# 19V_Converter.net
KiCad netlist of a schematic drawn in Altium Designer
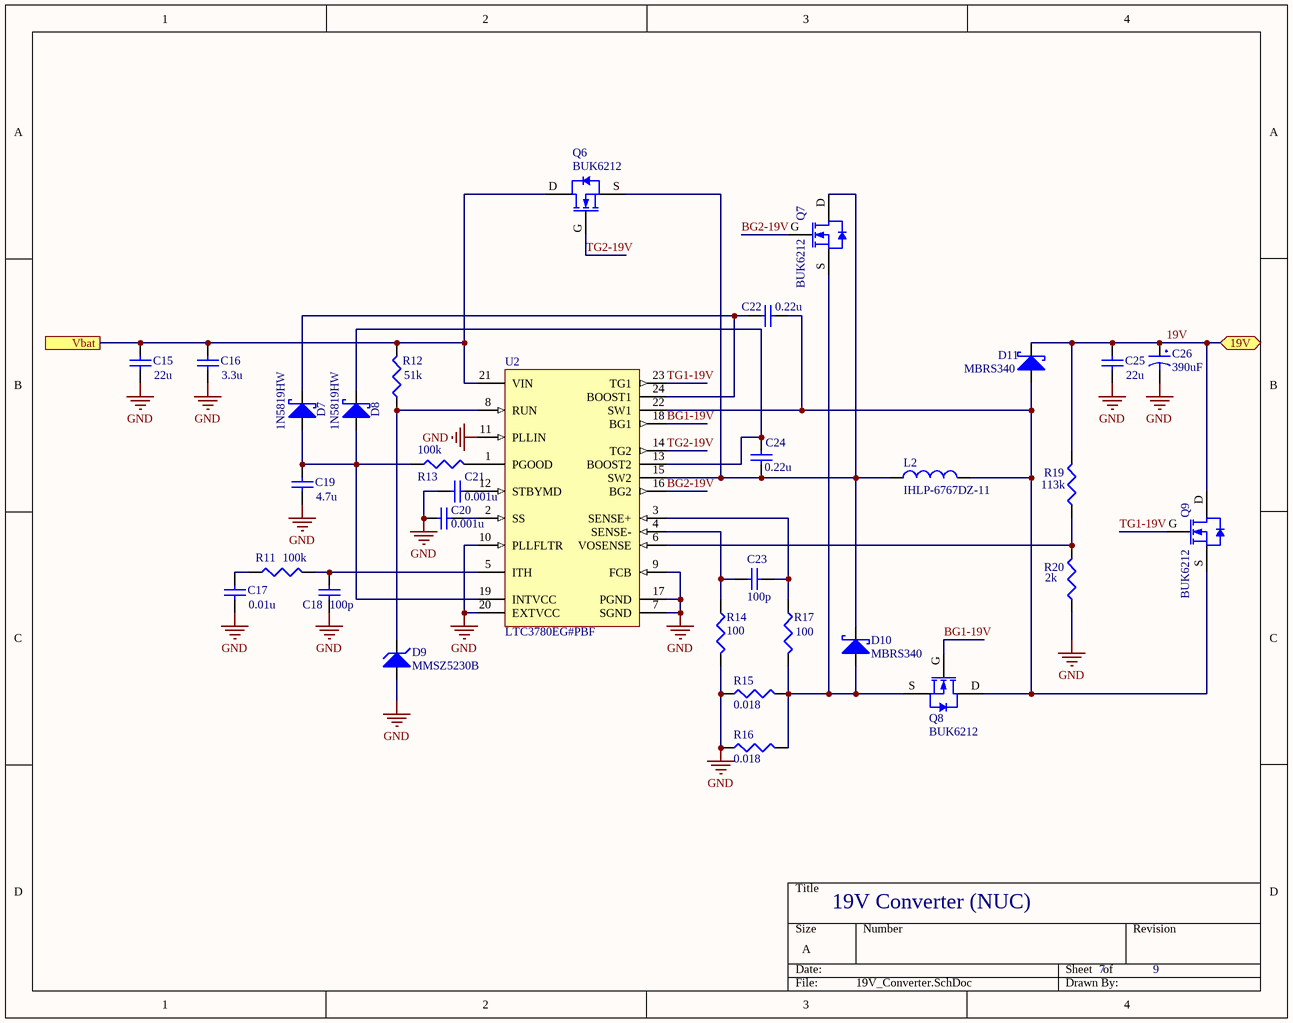
[diagram p0: 19V_Converter.SchDoc]

(export (version "E")
  (design (tool "Eeschema 10.0.6"))
  (components
    (comp (ref "C15")
      (value "22u")
      (footprint "C1206")
      (description "Capacitor (Semiconductor SIM Model)")
      (fields (field (name "Comment") "Cap Semi") (field (name "PUBLISHER") "Altium Limited"))
      (libsource (lib "Miscellaneous Devices") (part "Cap Semi"))
    )
    (comp (ref "C16")
      (value "3.3u")
      (footprint "C1206")
      (description "Capacitor (Semiconductor SIM Model)")
      (fields (field (name "Comment") "Cap Semi") (field (name "PUBLISHER") "Altium Limited"))
      (libsource (lib "Miscellaneous Devices") (part "Cap Semi"))
    )
    (comp (ref "C17")
      (value "0.01u")
      (footprint "C1206")
      (description "Capacitor (Semiconductor SIM Model)")
      (fields (field (name "Comment") "Cap Semi") (field (name "PUBLISHER") "Altium Limited"))
      (libsource (lib "Miscellaneous Devices") (part "Cap Semi"))
    )
    (comp (ref "C18")
      (value "100p")
      (footprint "C1206")
      (description "Capacitor (Semiconductor SIM Model)")
      (fields (field (name "Comment") "Cap Semi") (field (name "PUBLISHER") "Altium Limited"))
      (libsource (lib "Miscellaneous Devices") (part "Cap Semi"))
    )
    (comp (ref "C19")
      (value "4.7u")
      (footprint "C1206")
      (description "Capacitor (Semiconductor SIM Model)")
      (fields (field (name "Comment") "Cap Semi") (field (name "PUBLISHER") "Altium Limited"))
      (libsource (lib "Miscellaneous Devices") (part "Cap Semi"))
    )
    (comp (ref "C20")
      (value "0.001u")
      (footprint "C1206")
      (description "Capacitor (Semiconductor SIM Model)")
      (fields (field (name "Comment") "Cap Semi") (field (name "PUBLISHER") "Altium Limited"))
      (libsource (lib "Miscellaneous Devices") (part "Cap Semi"))
    )
    (comp (ref "C21")
      (value "0.001u")
      (footprint "C1206")
      (description "Capacitor (Semiconductor SIM Model)")
      (fields (field (name "Comment") "Cap Semi") (field (name "PUBLISHER") "Altium Limited"))
      (libsource (lib "Miscellaneous Devices") (part "Cap Semi"))
    )
    (comp (ref "C22")
      (value "0.22u")
      (footprint "C1206")
      (description "Capacitor (Semiconductor SIM Model)")
      (fields (field (name "Comment") "Cap Semi") (field (name "PUBLISHER") "Altium Limited"))
      (libsource (lib "Miscellaneous Devices") (part "Cap Semi"))
    )
    (comp (ref "C23")
      (value "100p")
      (footprint "C1206")
      (description "Capacitor (Semiconductor SIM Model)")
      (fields (field (name "Comment") "Cap Semi") (field (name "PUBLISHER") "Altium Limited"))
      (libsource (lib "Miscellaneous Devices") (part "Cap Semi"))
    )
    (comp (ref "C24")
      (value "0.22u")
      (footprint "C1206")
      (description "Capacitor (Semiconductor SIM Model)")
      (fields (field (name "Comment") "Cap Semi") (field (name "PUBLISHER") "Altium Limited"))
      (libsource (lib "Miscellaneous Devices") (part "Cap Semi"))
    )
    (comp (ref "C25")
      (value "22u")
      (footprint "C1206")
      (description "Capacitor (Semiconductor SIM Model)")
      (fields (field (name "Comment") "Cap Semi") (field (name "PUBLISHER") "Altium Limited"))
      (libsource (lib "Miscellaneous Devices") (part "Cap Semi"))
    )
    (comp (ref "C26")
      (value "390uF")
      (footprint "PCVxxxxxMCLxGS")
      (description "CAP ALUM POLY 390UF 20% 25V SMD")
      (libsource (lib "Power_Embedded_Board_Library") (part "PCV1E391MCL2GS"))
    )
    (comp (ref "D7")
      (value "1N5819HW")
      (footprint "1N58xx")
      (description "1A Schottky Barrier Rectifier Diode")
      (libsource (lib "Power_Embedded_Board_Library") (part "1N58xx"))
    )
    (comp (ref "D8")
      (value "1N5819HW")
      (footprint "1N58xx")
      (description "1A Schottky Barrier Rectifier Diode")
      (libsource (lib "Power_Embedded_Board_Library") (part "1N58xx"))
    )
    (comp (ref "D9")
      (value "MMSZ5230B")
      (footprint "ONSC-SOD-123-2-425-04_V")
      (description "Zener Voltage Regulator, 500 mW, 2-Pin SOD-123, Pb-Free, Tape and Reel")
      (fields (field (name "MANUFACTURER") "On Semiconductor") (field (name "PARTNUMBER") "MMSZ5230BT1G"))
      (libsource (lib "Power_Embedded_Board_Library") (part "MMSZ5230BT1G"))
    )
    (comp (ref "D10")
      (value "MBRS340")
      (footprint "MBRS340")
      (description "Schottky Rectifier")
      (libsource (lib "Power_Embedded_Board_Library") (part "MBRS340"))
    )
    (comp (ref "D11")
      (value "MBRS340")
      (footprint "MBRS340")
      (description "Schottky Rectifier")
      (libsource (lib "Power_Embedded_Board_Library") (part "MBRS340"))
    )
    (comp (ref "L2")
      (value "IHLP-6767DZ-11")
      (footprint "IHLP-6767DZ-11")
      (description "15µH Shielded Molded Inductor 14A 14.4 mOhm Max Nonstandard")
      (libsource (lib "Power_Embedded_Board_Library") (part "IHLP-6767DZ-11"))
    )
    (comp (ref "Q6")
      (value "BUK6212")
      (footprint "NXP-SOT428_M")
      (description "N-Channel TrenchMOS Intermediate Level FET, 40 V, 50 A, 3-Pin SOT428, Tape and Reel")
      (fields
        (field (name "MANUFACTURER") "NXP Semiconductors")
        (field (name "PARTNUMBER") "BUK6212-40C,118")
      )
      (libsource (lib "Power_Embedded_Board_Library") (part "BUK6212"))
    )
    (comp (ref "Q7")
      (value "BUK6212")
      (footprint "NXP-SOT428_M")
      (description "N-Channel TrenchMOS Intermediate Level FET, 40 V, 50 A, 3-Pin SOT428, Tape and Reel")
      (fields
        (field (name "MANUFACTURER") "NXP Semiconductors")
        (field (name "PARTNUMBER") "BUK6212-40C,118")
      )
      (libsource (lib "Power_Embedded_Board_Library") (part "BUK6212"))
    )
    (comp (ref "Q8")
      (value "BUK6212")
      (footprint "NXP-SOT428_M")
      (description "N-Channel TrenchMOS Intermediate Level FET, 40 V, 50 A, 3-Pin SOT428, Tape and Reel")
      (fields
        (field (name "MANUFACTURER") "NXP Semiconductors")
        (field (name "PARTNUMBER") "BUK6212-40C,118")
      )
      (libsource (lib "Power_Embedded_Board_Library") (part "BUK6212"))
    )
    (comp (ref "Q9")
      (value "BUK6212")
      (footprint "NXP-SOT428_M")
      (description "N-Channel TrenchMOS Intermediate Level FET, 40 V, 50 A, 3-Pin SOT428, Tape and Reel")
      (fields
        (field (name "MANUFACTURER") "NXP Semiconductors")
        (field (name "PARTNUMBER") "BUK6212-40C,118")
      )
      (libsource (lib "Power_Embedded_Board_Library") (part "BUK6212"))
    )
    (comp (ref "R11")
      (value "100k")
      (footprint "J1-0603")
      (description "Resistor")
      (fields (field (name "Comment") "Res3") (field (name "PUBLISHER") "Altium Limited"))
      (libsource (lib "Miscellaneous Devices") (part "Res3"))
    )
    (comp (ref "R12")
      (value "51k")
      (footprint "J1-0603")
      (description "Resistor")
      (fields (field (name "Comment") "Res3") (field (name "PUBLISHER") "Altium Limited"))
      (libsource (lib "Miscellaneous Devices") (part "Res3"))
    )
    (comp (ref "R13")
      (value "100k")
      (footprint "J1-0603")
      (description "Resistor")
      (fields (field (name "Comment") "Res3") (field (name "PUBLISHER") "Altium Limited"))
      (libsource (lib "Miscellaneous Devices") (part "Res3"))
    )
    (comp (ref "R14")
      (value "100")
      (footprint "J1-0603")
      (description "Resistor")
      (fields (field (name "Comment") "Res3") (field (name "PUBLISHER") "Altium Limited"))
      (libsource (lib "Miscellaneous Devices") (part "Res3"))
    )
    (comp (ref "R15")
      (value "0.018")
      (footprint "R1206")
      (description "Resistor")
      (fields (field (name "Comment") "Res3") (field (name "PUBLISHER") "Altium Limited"))
      (libsource (lib "Miscellaneous Devices") (part "Res3"))
    )
    (comp (ref "R16")
      (value "0.018")
      (footprint "R1206")
      (description "Resistor")
      (fields (field (name "Comment") "Res3") (field (name "PUBLISHER") "Altium Limited"))
      (libsource (lib "Miscellaneous Devices") (part "Res3"))
    )
    (comp (ref "R17")
      (value "100")
      (footprint "J1-0603")
      (description "Resistor")
      (fields (field (name "Comment") "Res3") (field (name "PUBLISHER") "Altium Limited"))
      (libsource (lib "Miscellaneous Devices") (part "Res3"))
    )
    (comp (ref "R19")
      (value "113k")
      (footprint "J1-0603")
      (description "Resistor")
      (fields (field (name "Comment") "Res3") (field (name "PUBLISHER") "Altium Limited"))
      (libsource (lib "Miscellaneous Devices") (part "Res3"))
    )
    (comp (ref "R20")
      (value "2k")
      (footprint "J1-0603")
      (description "Resistor")
      (fields (field (name "Comment") "Res3") (field (name "PUBLISHER") "Altium Limited"))
      (libsource (lib "Miscellaneous Devices") (part "Res3"))
    )
    (comp (ref "U2")
      (value "LTC3780EG#PBF")
      (footprint "LT-G-24_L")
      (fields (field (name "MANUFACTURER") "Linear Technology"))
      (libsource (lib "Power_Embedded_Board_Library") (part "LTC3780EG#PBF"))
    )
  )
  (nets
    (net (code "1") (name "/19V") (class "Default")
      (node (ref "C25") (pin "2") (pinfunction "2_2") (pintype "passive"))
      (node (ref "C26") (pin "1") (pinfunction "1_1") (pintype "passive"))
      (node (ref "D11") (pin "K") (pinfunction "Cathode_K") (pintype "passive"))
      (node (ref "Q9") (pin "D") (pinfunction "D_D") (pintype "passive"))
      (node (ref "R19") (pin "2") (pinfunction "2_2") (pintype "passive"))
    )
    (net (code "2") (name "/BG1-19V") (class "Default")
      (node (ref "Q8") (pin "G") (pinfunction "G_G") (pintype "passive"))
      (node (ref "U2") (pin "18") (pinfunction "BG1_18") (pintype "output"))
    )
    (net (code "3") (name "/BG2-19V") (class "Default")
      (node (ref "Q7") (pin "G") (pinfunction "G_G") (pintype "passive"))
      (node (ref "U2") (pin "16") (pinfunction "BG2_16") (pintype "output"))
    )
    (net (code "4") (name "/TG1-19V") (class "Default")
      (node (ref "Q9") (pin "G") (pinfunction "G_G") (pintype "passive"))
      (node (ref "U2") (pin "23") (pinfunction "TG1_23") (pintype "output"))
    )
    (net (code "5") (name "/TG2-19V") (class "Default")
      (node (ref "Q6") (pin "G") (pinfunction "G_G") (pintype "passive"))
      (node (ref "U2") (pin "14") (pinfunction "TG2_14") (pintype "output"))
    )
    (net (code "6") (name "/Vbat") (class "Default")
      (node (ref "C15") (pin "2") (pinfunction "2_2") (pintype "passive"))
      (node (ref "C16") (pin "2") (pinfunction "2_2") (pintype "passive"))
      (node (ref "Q6") (pin "D") (pinfunction "D_D") (pintype "passive"))
      (node (ref "R12") (pin "2") (pinfunction "2_2") (pintype "passive"))
      (node (ref "U2") (pin "21") (pinfunction "VIN_21") (pintype "power_in"))
    )
    (net (code "7") (name "GND") (class "Default")
      (node (ref "C15") (pin "1") (pinfunction "1_1") (pintype "passive"))
      (node (ref "C16") (pin "1") (pinfunction "1_1") (pintype "passive"))
      (node (ref "C17") (pin "1") (pinfunction "1_1") (pintype "passive"))
      (node (ref "C18") (pin "1") (pinfunction "1_1") (pintype "passive"))
      (node (ref "C19") (pin "1") (pinfunction "1_1") (pintype "passive"))
      (node (ref "C20") (pin "1") (pinfunction "1_1") (pintype "passive"))
      (node (ref "C21") (pin "1") (pinfunction "1_1") (pintype "passive"))
      (node (ref "C25") (pin "1") (pinfunction "1_1") (pintype "passive"))
      (node (ref "C26") (pin "2") (pinfunction "2_2") (pintype "passive"))
      (node (ref "D9") (pin "2") (pinfunction "A_2") (pintype "passive"))
      (node (ref "R14") (pin "2") (pinfunction "2_2") (pintype "passive"))
      (node (ref "R15") (pin "1") (pinfunction "1_1") (pintype "passive"))
      (node (ref "R16") (pin "1") (pinfunction "1_1") (pintype "passive"))
      (node (ref "R20") (pin "1") (pinfunction "1_1") (pintype "passive"))
      (node (ref "U2") (pin "10") (pinfunction "PLLFLTR_10") (pintype "input"))
      (node (ref "U2") (pin "11") (pinfunction "PLLIN_11") (pintype "input"))
      (node (ref "U2") (pin "17") (pinfunction "PGND_17") (pintype "power_in"))
      (node (ref "U2") (pin "20") (pinfunction "EXTVCC_20") (pintype "power_in"))
      (node (ref "U2") (pin "7") (pinfunction "SGND_7") (pintype "power_in"))
      (node (ref "U2") (pin "9") (pinfunction "FCB_9") (pintype "input"))
    )
    (net (code "8") (name "Net-(C17-Pad2)") (class "Default")
      (node (ref "C17") (pin "2") (pinfunction "2_2") (pintype "passive"))
      (node (ref "R11") (pin "1") (pinfunction "1_1") (pintype "passive"))
    )
    (net (code "9") (name "Net-(D7-Anode)") (class "Default")
      (node (ref "C19") (pin "2") (pinfunction "2_2") (pintype "passive"))
      (node (ref "D7") (pin "A") (pinfunction "Anode_A") (pintype "passive"))
      (node (ref "D8") (pin "A") (pinfunction "Anode_A") (pintype "passive"))
      (node (ref "R13") (pin "1") (pinfunction "1_1") (pintype "passive"))
      (node (ref "U2") (pin "19") (pinfunction "INTVCC_19") (pintype "power_in"))
    )
    (net (code "10") (name "Net-(D7-Cathode)") (class "Default")
      (node (ref "C22") (pin "2") (pinfunction "2_2") (pintype "passive"))
      (node (ref "D7") (pin "K") (pinfunction "Cathode_K") (pintype "passive"))
      (node (ref "U2") (pin "24") (pinfunction "BOOST1_24") (pintype "passive"))
    )
    (net (code "11") (name "Net-(D8-Cathode)") (class "Default")
      (node (ref "C24") (pin "2") (pinfunction "2_2") (pintype "passive"))
      (node (ref "D8") (pin "K") (pinfunction "Cathode_K") (pintype "passive"))
      (node (ref "U2") (pin "13") (pinfunction "BOOST2_13") (pintype "passive"))
    )
    (net (code "12") (name "Net-(D9-K)") (class "Default")
      (node (ref "D9") (pin "1") (pinfunction "K_1") (pintype "passive"))
      (node (ref "R12") (pin "1") (pinfunction "1_1") (pintype "passive"))
      (node (ref "U2") (pin "8") (pinfunction "RUN_8") (pintype "input"))
    )
    (net (code "13") (name "Net-(D10-Anode)") (class "Default")
      (node (ref "D10") (pin "A") (pinfunction "Anode_A") (pintype "passive"))
      (node (ref "Q7") (pin "S") (pinfunction "S_S") (pintype "passive"))
      (node (ref "Q8") (pin "S") (pinfunction "S_S") (pintype "passive"))
      (node (ref "R15") (pin "2") (pinfunction "2_2") (pintype "passive"))
      (node (ref "R16") (pin "2") (pinfunction "2_2") (pintype "passive"))
      (node (ref "R17") (pin "2") (pinfunction "2_2") (pintype "passive"))
    )
    (net (code "14") (name "Net-(D10-Cathode)") (class "Default")
      (node (ref "C24") (pin "1") (pinfunction "1_1") (pintype "passive"))
      (node (ref "D10") (pin "K") (pinfunction "Cathode_K") (pintype "passive"))
      (node (ref "L2") (pin "1") (pinfunction "1_1") (pintype "passive"))
      (node (ref "Q6") (pin "S") (pinfunction "S_S") (pintype "passive"))
      (node (ref "Q7") (pin "D") (pinfunction "D_D") (pintype "passive"))
      (node (ref "U2") (pin "15") (pinfunction "SW2_15") (pintype "passive"))
    )
    (net (code "15") (name "Net-(D11-Anode)") (class "Default")
      (node (ref "C22") (pin "1") (pinfunction "1_1") (pintype "passive"))
      (node (ref "D11") (pin "A") (pinfunction "Anode_A") (pintype "passive"))
      (node (ref "L2") (pin "2") (pinfunction "2_2") (pintype "passive"))
      (node (ref "Q8") (pin "D") (pinfunction "D_D") (pintype "passive"))
      (node (ref "Q9") (pin "S") (pinfunction "S_S") (pintype "passive"))
      (node (ref "U2") (pin "22") (pinfunction "SW1_22") (pintype "passive"))
    )
    (net (code "16") (name "Net-(U2-ITH)") (class "Default")
      (node (ref "C18") (pin "2") (pinfunction "2_2") (pintype "passive"))
      (node (ref "R11") (pin "2") (pinfunction "2_2") (pintype "passive"))
      (node (ref "U2") (pin "5") (pinfunction "ITH_5") (pintype "passive"))
    )
    (net (code "17") (name "Net-(U2-PGOOD)") (class "Default")
      (node (ref "R13") (pin "2") (pinfunction "2_2") (pintype "passive"))
      (node (ref "U2") (pin "1") (pinfunction "PGOOD_1") (pintype "open_collector"))
    )
    (net (code "18") (name "Net-(U2-SENSE+)") (class "Default")
      (node (ref "C23") (pin "2") (pinfunction "2_2") (pintype "passive"))
      (node (ref "R17") (pin "1") (pinfunction "1_1") (pintype "passive"))
      (node (ref "U2") (pin "3") (pinfunction "SENSE+_3") (pintype "input"))
    )
    (net (code "19") (name "Net-(U2-SENSE-)") (class "Default")
      (node (ref "C23") (pin "1") (pinfunction "1_1") (pintype "passive"))
      (node (ref "R14") (pin "1") (pinfunction "1_1") (pintype "passive"))
      (node (ref "U2") (pin "4") (pinfunction "SENSE-_4") (pintype "input"))
    )
    (net (code "20") (name "Net-(U2-SS)") (class "Default")
      (node (ref "C20") (pin "2") (pinfunction "2_2") (pintype "passive"))
      (node (ref "U2") (pin "2") (pinfunction "SS_2") (pintype "input"))
    )
    (net (code "21") (name "Net-(U2-STBYMD)") (class "Default")
      (node (ref "C21") (pin "2") (pinfunction "2_2") (pintype "passive"))
      (node (ref "U2") (pin "12") (pinfunction "STBYMD_12") (pintype "input"))
    )
    (net (code "22") (name "Net-(U2-VOSENSE)") (class "Default")
      (node (ref "R19") (pin "1") (pinfunction "1_1") (pintype "passive"))
      (node (ref "R20") (pin "2") (pinfunction "2_2") (pintype "passive"))
      (node (ref "U2") (pin "6") (pinfunction "VOSENSE_6") (pintype "input"))
    )
  )
)
